# QCopterRC_USB_Sch.net
KiCad netlist of a schematic drawn in Altium Designer
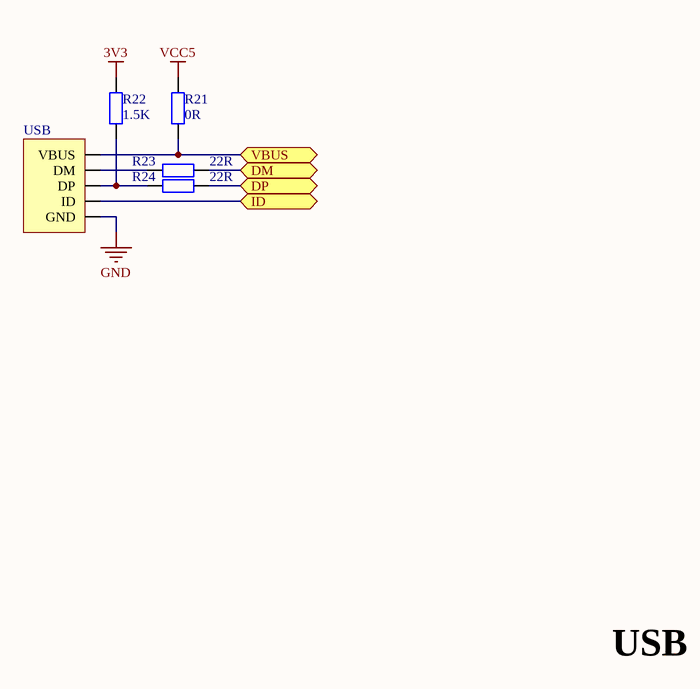
[diagram p0: QCopterRC_USB_Sch.SchDoc]

(export (version "E")
  (design (tool "Eeschema 10.0.6"))
  (components
    (comp (ref "R21")
      (value "0R")
      (footprint "PCB_Passive:RES_0603")
      (description "Resistor")
      (fields (field (name "Comment") "Res_0603"))
      (libsource (lib "") (part "Res_0603_1"))
    )
    (comp (ref "R22")
      (value "1.5K")
      (footprint "PCB_Passive:RES_0603")
      (description "Resistor")
      (fields (field (name "Comment") "Res_0603"))
      (libsource (lib "") (part "Res_0603_2"))
    )
    (comp (ref "R23")
      (value "22R")
      (footprint "PCB_Passive:RES_0603")
      (description "Resistor")
      (fields (field (name "Comment") "Res_0603"))
      (libsource (lib "SCH_Passive") (part "Res_0603"))
    )
    (comp (ref "R24")
      (value "22R")
      (footprint "PCB_Passive:RES_0603")
      (description "Resistor")
      (fields (field (name "Comment") "Res_0603"))
      (libsource (lib "SCH_Passive") (part "Res_0603"))
    )
    (comp (ref "USB")
      (value "USB_Micro")
      (footprint "PCB_USB:USB_MICRO_B")
      (description "USB")
      (libsource (lib "SCH_USB") (part "USB_Micro"))
    )
  )
  (nets
    (net (code "1") (name "/DM") (class "Default")
      (node (ref "R23") (pin "2") (pinfunction "2_2") (pintype "passive"))
    )
    (net (code "2") (name "/DP") (class "Default")
      (node (ref "R24") (pin "2") (pinfunction "2_2") (pintype "passive"))
    )
    (net (code "3") (name "/ID") (class "Default")
      (node (ref "USB") (pin "4") (pinfunction "ID_4") (pintype "passive"))
    )
    (net (code "4") (name "/VBUS") (class "Default")
      (node (ref "R21") (pin "2") (pinfunction "2_2") (pintype "passive"))
      (node (ref "USB") (pin "1") (pinfunction "VBUS_1") (pintype "passive"))
    )
    (net (code "5") (name "3V3") (class "Default")
      (node (ref "R22") (pin "2") (pinfunction "2_2") (pintype "passive"))
    )
    (net (code "6") (name "GND") (class "Default")
      (node (ref "USB") (pin "5") (pinfunction "GND_5") (pintype "passive"))
    )
    (net (code "7") (name "Net-(USB-DM)") (class "Default")
      (node (ref "R23") (pin "1") (pinfunction "1_1") (pintype "passive"))
      (node (ref "USB") (pin "2") (pinfunction "DM_2") (pintype "passive"))
    )
    (net (code "8") (name "Net-(USB-DP)") (class "Default")
      (node (ref "R22") (pin "1") (pinfunction "1_1") (pintype "passive"))
      (node (ref "R24") (pin "1") (pinfunction "1_1") (pintype "passive"))
      (node (ref "USB") (pin "3") (pinfunction "DP_3") (pintype "passive"))
    )
    (net (code "9") (name "VCC5") (class "Default")
      (node (ref "R21") (pin "1") (pinfunction "1_1") (pintype "passive"))
    )
  )
)
